# Dazzle_v1.net
KiCad netlist of a schematic drawn in EAGLE
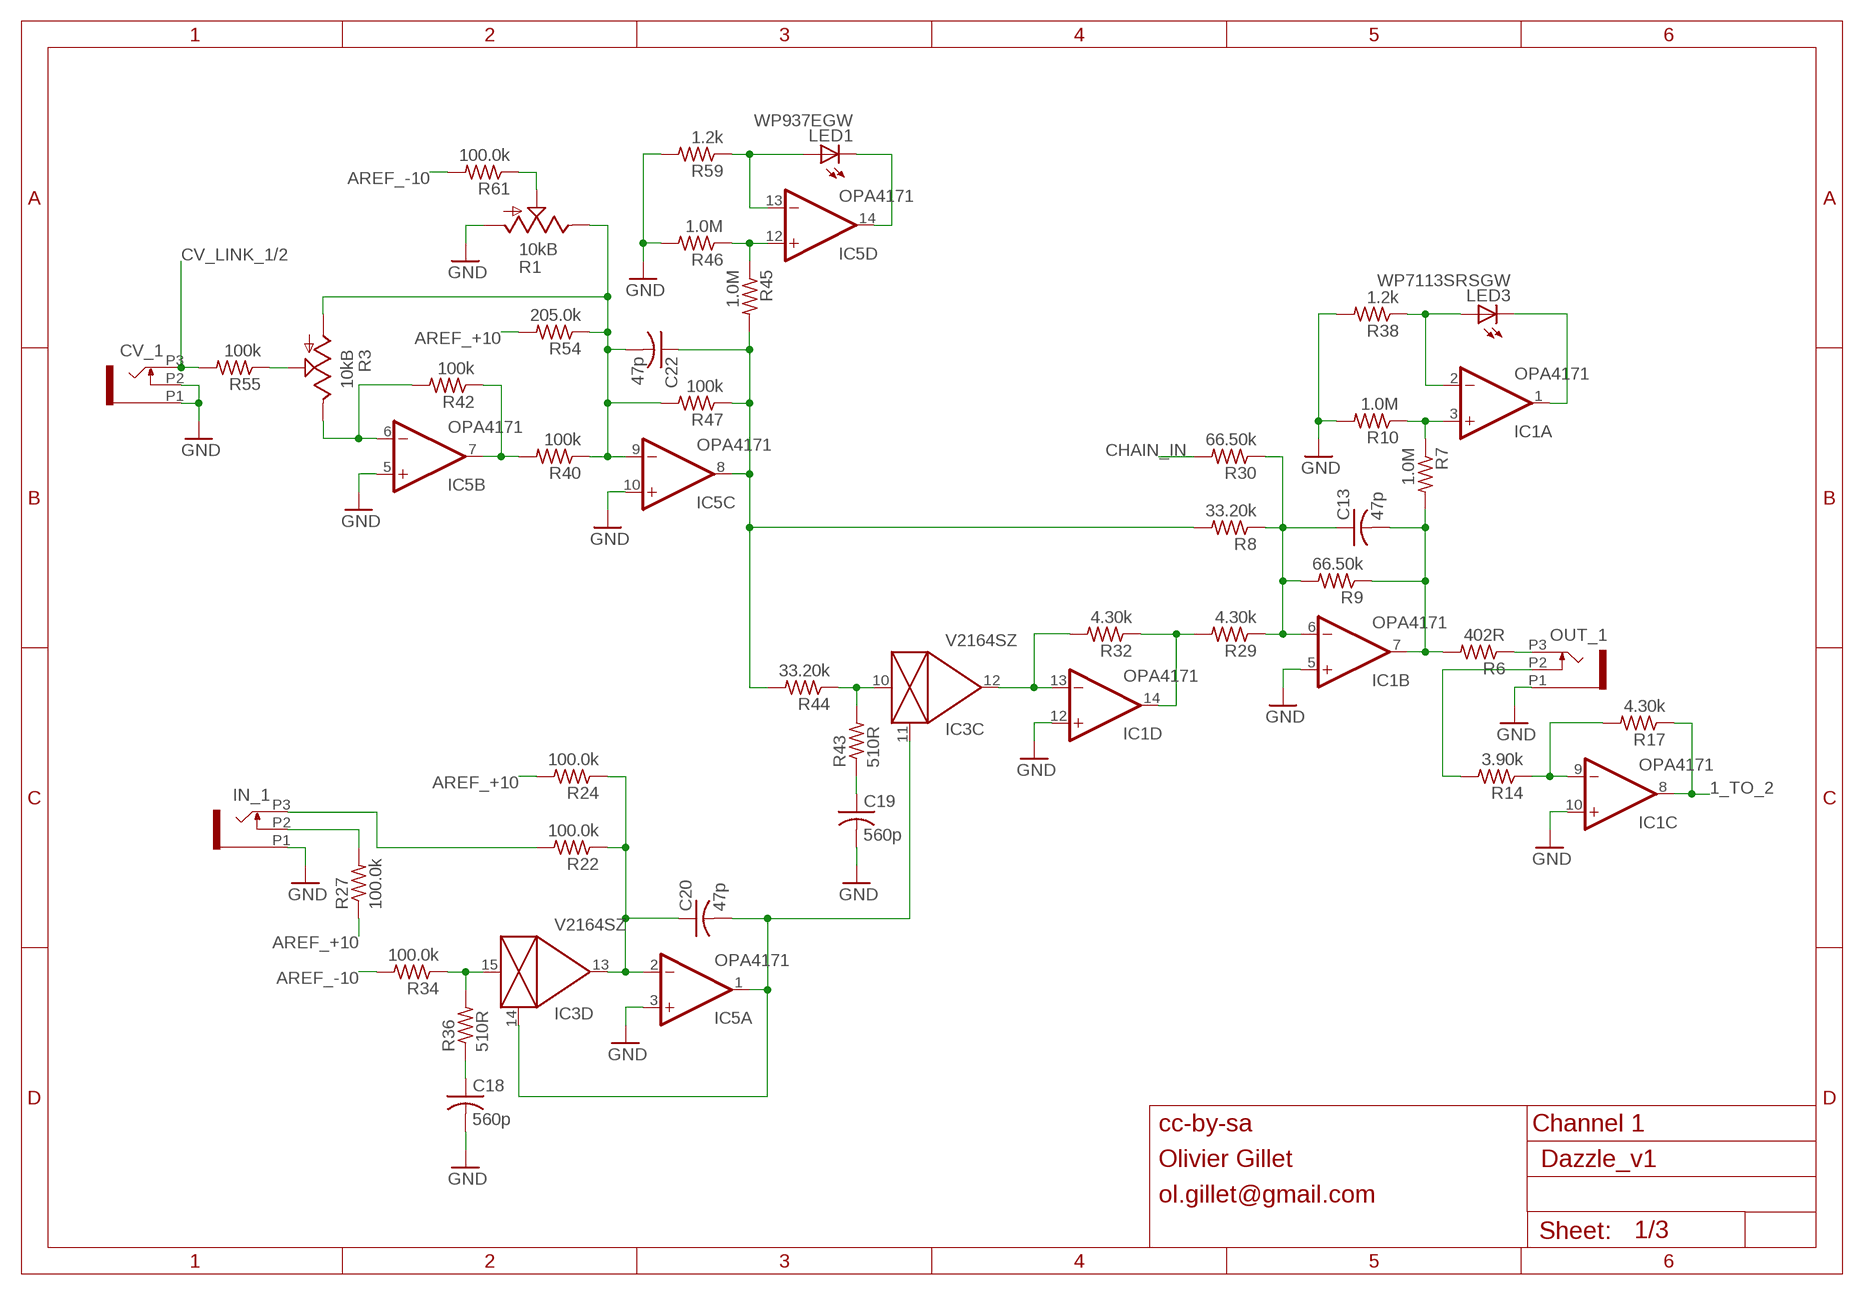
[diagram p0: schematic, sheet 1]
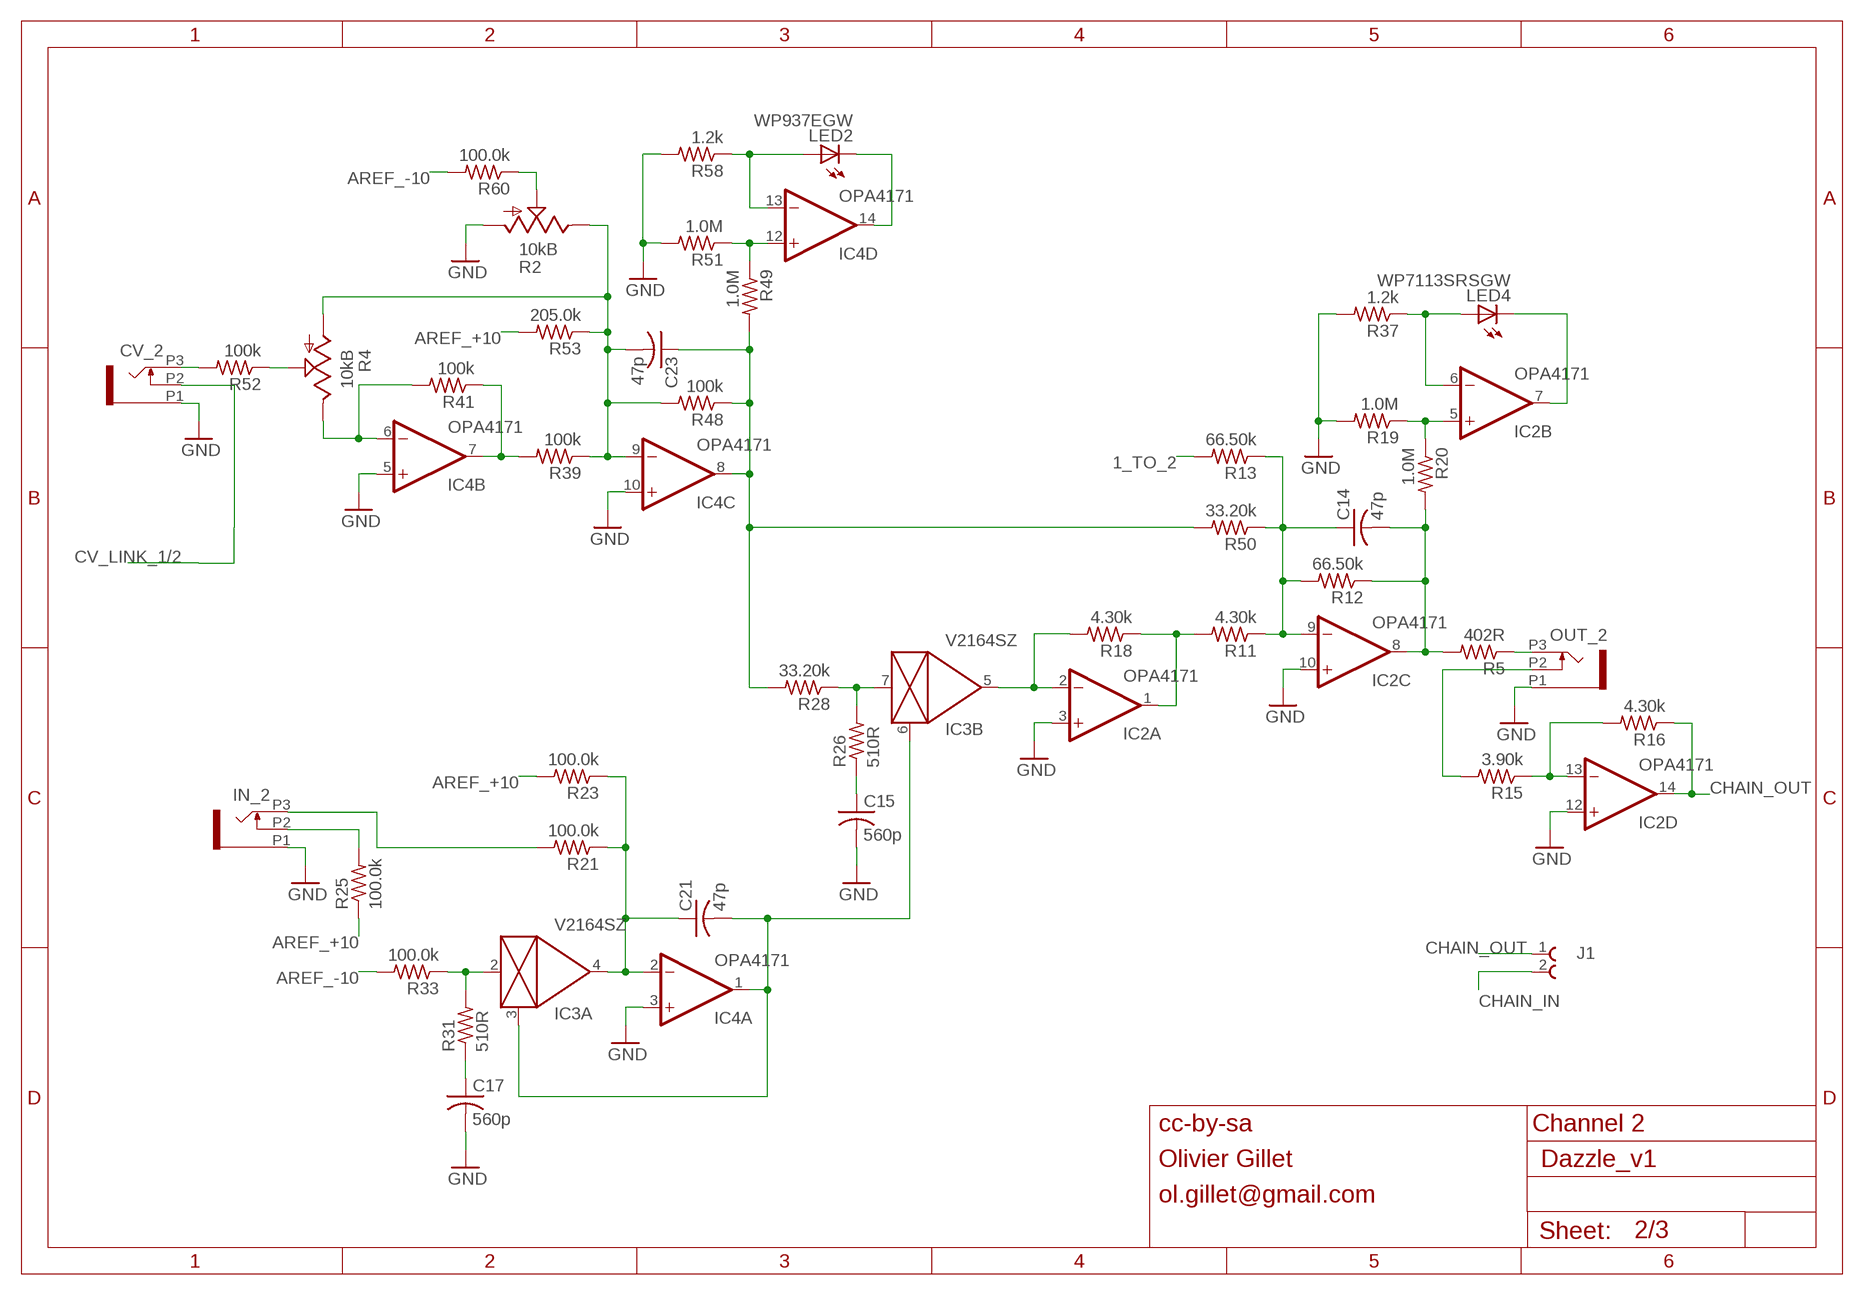
[diagram p1: schematic, sheet 2]
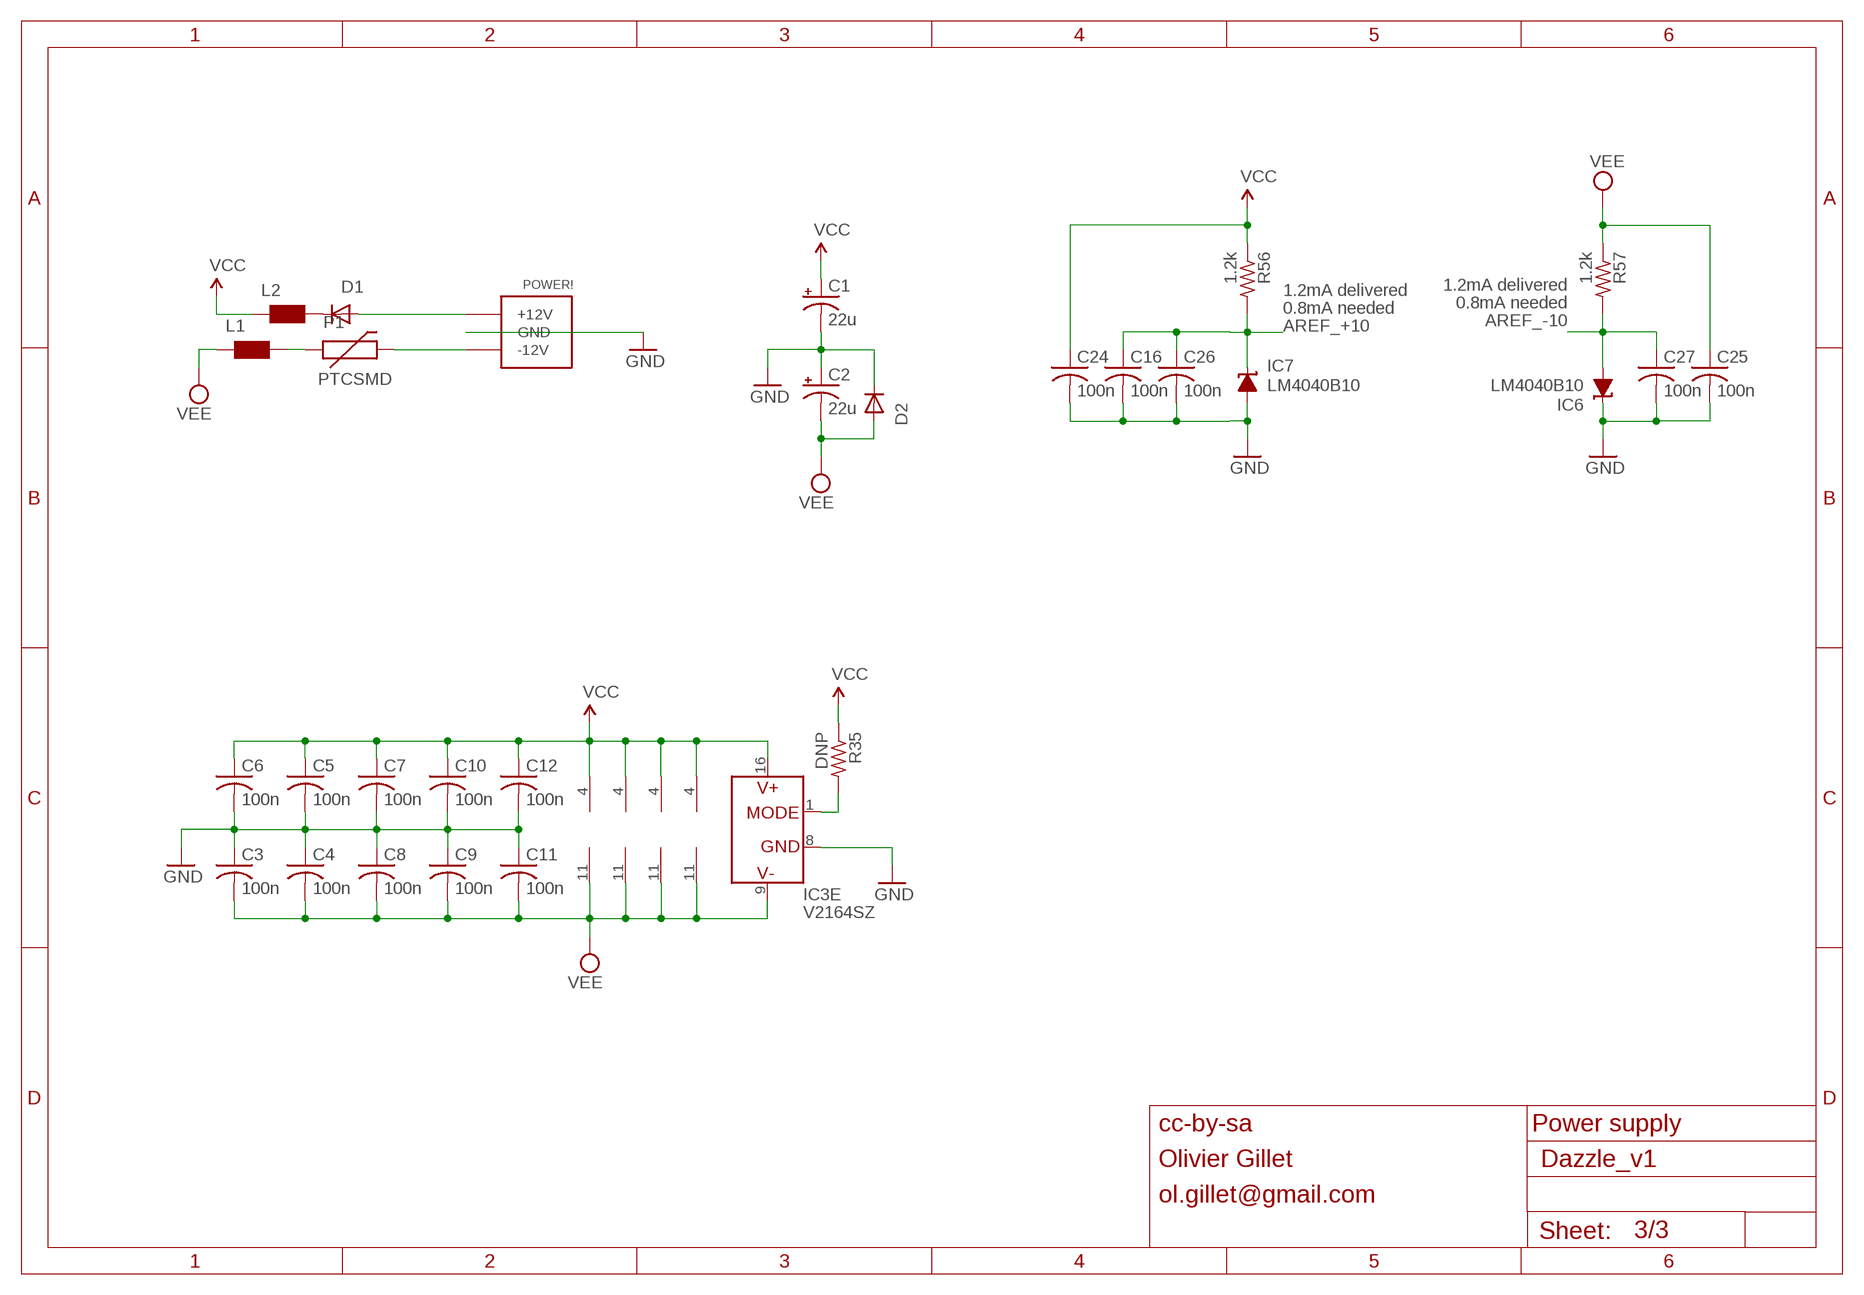
[diagram p2: schematic, sheet 3]

(export (version "E")
  (design (tool "Eeschema 10.0.6"))
  (components
    (comp (ref "C13")
      (value "47p")
      (footprint "eagle-import:C0603")
      (libsource (lib "eagle-import") (part "C-USC0603"))
    )
    (comp (ref "C18")
      (value "560p")
      (footprint "eagle-import:C0603")
      (libsource (lib "eagle-import") (part "C-USC0603"))
    )
    (comp (ref "C19")
      (value "560p")
      (footprint "eagle-import:C0603")
      (libsource (lib "eagle-import") (part "C-USC0603"))
    )
    (comp (ref "C20")
      (value "47p")
      (footprint "eagle-import:C0603")
      (libsource (lib "eagle-import") (part "C-USC0603"))
    )
    (comp (ref "C22")
      (value "47p")
      (footprint "eagle-import:C0603")
      (libsource (lib "eagle-import") (part "C-USC0603"))
    )
    (comp (ref "CV_1")
      (value "OG-PJ301_PJ301_THONKICONN")
      (footprint "eagle-import:OG-PJ301_WQP_PJ_301M6_NO_HOLE")
      (libsource (lib "eagle-import") (part "OG-PJ301_PJ301_THONKICONN"))
    )
    (comp (ref "IC1")
      (value "OPA4171")
      (footprint "eagle-import:TSSOP14")
      (libsource (lib "eagle-import") (part "TL074PW"))
    )
    (comp (ref "IC3")
      (value "V2164SZ")
      (footprint "eagle-import:SOIC16N")
      (libsource (lib "eagle-import") (part "SSM2164S"))
    )
    (comp (ref "IC5")
      (value "OPA4171")
      (footprint "eagle-import:TSSOP14")
      (libsource (lib "eagle-import") (part "TL074PW"))
    )
    (comp (ref "IN_1")
      (value "OG-PJ301_PJ301_THONKICONN")
      (footprint "eagle-import:OG-PJ301_WQP_PJ_301M6_NO_HOLE")
      (libsource (lib "eagle-import") (part "OG-PJ301_PJ301_THONKICONN"))
    )
    (comp (ref "LED1")
      (value "WP937EGW")
      (footprint "eagle-import:LED3MM")
      (libsource (lib "eagle-import") (part "LED3MM"))
    )
    (comp (ref "LED3")
      (value "WP7113SRSGW")
      (footprint "eagle-import:LED5MM")
      (libsource (lib "eagle-import") (part "LED5MM"))
    )
    (comp (ref "OUT_1")
      (value "OG-PJ301_PJ301_THONKICONN")
      (footprint "eagle-import:OG-PJ301_WQP_PJ_301M6_NO_HOLE")
      (libsource (lib "eagle-import") (part "OG-PJ301_PJ301_THONKICONN"))
    )
    (comp (ref "R1")
      (value "10kB")
      (footprint "eagle-import:ALPS_POT_VERTICAL_PS")
      (libsource (lib "eagle-import") (part "POT_USVERTICAL_PS"))
    )
    (comp (ref "R3")
      (value "10kB")
      (footprint "eagle-import:POT-ALPS_ALPS_POT_VERTICAL_PS")
      (libsource (lib "eagle-import") (part "POT-ALPS_POT_USVERTICAL_PS"))
    )
    (comp (ref "R6")
      (value "402R")
      (footprint "eagle-import:R0603")
      (libsource (lib "eagle-import") (part "R-US_R0603"))
    )
    (comp (ref "R7")
      (value "1.0M")
      (footprint "eagle-import:R0603")
      (libsource (lib "eagle-import") (part "R-US_R0603"))
    )
    (comp (ref "R8")
      (value "33.20k")
      (footprint "eagle-import:R0603")
      (libsource (lib "eagle-import") (part "R-US_R0603"))
    )
    (comp (ref "R9")
      (value "66.50k")
      (footprint "eagle-import:R0603")
      (libsource (lib "eagle-import") (part "R-US_R0603"))
    )
    (comp (ref "R10")
      (value "1.0M")
      (footprint "eagle-import:R0603")
      (libsource (lib "eagle-import") (part "R-US_R0603"))
    )
    (comp (ref "R14")
      (value "3.90k")
      (footprint "eagle-import:R0603")
      (libsource (lib "eagle-import") (part "R-US_R0603"))
    )
    (comp (ref "R17")
      (value "4.30k")
      (footprint "eagle-import:R0603")
      (libsource (lib "eagle-import") (part "R-US_R0603"))
    )
    (comp (ref "R22")
      (value "100.0k")
      (footprint "eagle-import:R0603")
      (libsource (lib "eagle-import") (part "R-US_R0603"))
    )
    (comp (ref "R24")
      (value "100.0k")
      (footprint "eagle-import:R0603")
      (libsource (lib "eagle-import") (part "R-US_R0603"))
    )
    (comp (ref "R27")
      (value "100.0k")
      (footprint "eagle-import:R0603")
      (libsource (lib "eagle-import") (part "R-US_R0603"))
    )
    (comp (ref "R29")
      (value "4.30k")
      (footprint "eagle-import:R0603")
      (libsource (lib "eagle-import") (part "R-US_R0603"))
    )
    (comp (ref "R30")
      (value "66.50k")
      (footprint "eagle-import:R0603")
      (libsource (lib "eagle-import") (part "R-US_R0603"))
    )
    (comp (ref "R32")
      (value "4.30k")
      (footprint "eagle-import:R0603")
      (libsource (lib "eagle-import") (part "R-US_R0603"))
    )
    (comp (ref "R34")
      (value "100.0k")
      (footprint "eagle-import:R0603")
      (libsource (lib "eagle-import") (part "R-US_R0603"))
    )
    (comp (ref "R36")
      (value "510R")
      (footprint "eagle-import:R0603")
      (libsource (lib "eagle-import") (part "R-US_R0603"))
    )
    (comp (ref "R38")
      (value "1.2k")
      (footprint "eagle-import:R0603")
      (libsource (lib "eagle-import") (part "R-US_R0603"))
    )
    (comp (ref "R40")
      (value "100k")
      (footprint "eagle-import:R0603")
      (libsource (lib "eagle-import") (part "R-US_R0603"))
    )
    (comp (ref "R42")
      (value "100k")
      (footprint "eagle-import:R0603")
      (libsource (lib "eagle-import") (part "R-US_R0603"))
    )
    (comp (ref "R43")
      (value "510R")
      (footprint "eagle-import:R0603")
      (libsource (lib "eagle-import") (part "R-US_R0603"))
    )
    (comp (ref "R44")
      (value "33.20k")
      (footprint "eagle-import:R0603")
      (libsource (lib "eagle-import") (part "R-US_R0603"))
    )
    (comp (ref "R45")
      (value "1.0M")
      (footprint "eagle-import:R0603")
      (libsource (lib "eagle-import") (part "R-US_R0603"))
    )
    (comp (ref "R46")
      (value "1.0M")
      (footprint "eagle-import:R0603")
      (libsource (lib "eagle-import") (part "R-US_R0603"))
    )
    (comp (ref "R47")
      (value "100k")
      (footprint "eagle-import:R0603")
      (libsource (lib "eagle-import") (part "R-US_R0603"))
    )
    (comp (ref "R54")
      (value "205.0k")
      (footprint "eagle-import:R0603")
      (libsource (lib "eagle-import") (part "R-US_R0603"))
    )
    (comp (ref "R55")
      (value "100k")
      (footprint "eagle-import:R0603")
      (libsource (lib "eagle-import") (part "R-US_R0603"))
    )
    (comp (ref "R59")
      (value "1.2k")
      (footprint "eagle-import:R0603")
      (libsource (lib "eagle-import") (part "R-US_R0603"))
    )
    (comp (ref "R61")
      (value "100.0k")
      (footprint "eagle-import:R0603")
      (libsource (lib "eagle-import") (part "R-US_R0603"))
    )
    (comp (ref "C1")
      (value "22u")
      (footprint "eagle-import:PANASONIC_C")
      (libsource (lib "eagle-import") (part "CPOL-USC"))
    )
    (comp (ref "C2")
      (value "22u")
      (footprint "eagle-import:PANASONIC_C")
      (libsource (lib "eagle-import") (part "CPOL-USC"))
    )
    (comp (ref "C3")
      (value "100n")
      (footprint "eagle-import:C0603")
      (libsource (lib "eagle-import") (part "C-USC0603"))
    )
    (comp (ref "C4")
      (value "100n")
      (footprint "eagle-import:C0603")
      (libsource (lib "eagle-import") (part "C-USC0603"))
    )
    (comp (ref "C5")
      (value "100n")
      (footprint "eagle-import:C0603")
      (libsource (lib "eagle-import") (part "C-USC0603"))
    )
    (comp (ref "C6")
      (value "100n")
      (footprint "eagle-import:C0603")
      (libsource (lib "eagle-import") (part "C-USC0603"))
    )
    (comp (ref "C7")
      (value "100n")
      (footprint "eagle-import:C0603")
      (libsource (lib "eagle-import") (part "C-USC0603"))
    )
    (comp (ref "C8")
      (value "100n")
      (footprint "eagle-import:C0603")
      (libsource (lib "eagle-import") (part "C-USC0603"))
    )
    (comp (ref "C9")
      (value "100n")
      (footprint "eagle-import:C0603")
      (libsource (lib "eagle-import") (part "C-USC0603"))
    )
    (comp (ref "C10")
      (value "100n")
      (footprint "eagle-import:C0603")
      (libsource (lib "eagle-import") (part "C-USC0603"))
    )
    (comp (ref "C11")
      (value "100n")
      (footprint "eagle-import:C0603")
      (libsource (lib "eagle-import") (part "C-USC0603"))
    )
    (comp (ref "C12")
      (value "100n")
      (footprint "eagle-import:C0603")
      (libsource (lib "eagle-import") (part "C-USC0603"))
    )
    (comp (ref "C16")
      (value "100n")
      (footprint "eagle-import:C0603")
      (libsource (lib "eagle-import") (part "C-USC0603"))
    )
    (comp (ref "C24")
      (value "100n")
      (footprint "eagle-import:C0603")
      (libsource (lib "eagle-import") (part "C-USC0603"))
    )
    (comp (ref "C25")
      (value "100n")
      (footprint "eagle-import:C0603")
      (libsource (lib "eagle-import") (part "C-USC0603"))
    )
    (comp (ref "C26")
      (value "100n")
      (footprint "eagle-import:C0603")
      (libsource (lib "eagle-import") (part "C-USC0603"))
    )
    (comp (ref "C27")
      (value "100n")
      (footprint "eagle-import:C0603")
      (libsource (lib "eagle-import") (part "C-USC0603"))
    )
    (comp (ref "D1")
      (value "1N5819HW")
      (footprint "eagle-import:SOD123")
      (libsource (lib "eagle-import") (part "DIODE-SOD123"))
    )
    (comp (ref "D2")
      (value "1N5819HW")
      (footprint "eagle-import:SOD123")
      (libsource (lib "eagle-import") (part "DIODE-SOD123"))
    )
    (comp (ref "IC2")
      (value "OPA4171")
      (footprint "eagle-import:TSSOP14")
      (libsource (lib "eagle-import") (part "TL074PW"))
    )
    (comp (ref "IC4")
      (value "OPA4171")
      (footprint "eagle-import:TSSOP14")
      (libsource (lib "eagle-import") (part "TL074PW"))
    )
    (comp (ref "IC6")
      (value "LM4040B10")
      (footprint "eagle-import:DBZ_R-PDSO-G3")
      (libsource (lib "eagle-import") (part "LM4041DBZB12"))
    )
    (comp (ref "IC7")
      (value "LM4040B10")
      (footprint "eagle-import:DBZ_R-PDSO-G3")
      (libsource (lib "eagle-import") (part "LM4041DBZB12"))
    )
    (comp (ref "L1")
      (value "WE-CBF_0603")
      (footprint "eagle-import:0603")
      (libsource (lib "eagle-import") (part "WE-CBF_0603"))
    )
    (comp (ref "L2")
      (value "WE-CBF_0603")
      (footprint "eagle-import:0603")
      (libsource (lib "eagle-import") (part "WE-CBF_0603"))
    )
    (comp (ref "P1")
      (value "PTCSMD")
      (footprint "eagle-import:PTC-1206")
      (libsource (lib "eagle-import") (part "PTCSMD"))
    )
    (comp (ref "POWER!")
      (value "POWER_SIMPLE")
      (footprint "eagle-import:2X05_SMT_HEADER")
      (libsource (lib "eagle-import") (part "POWER_SIMPLE"))
    )
    (comp (ref "R35")
      (value "DNP")
      (footprint "eagle-import:R0603")
      (libsource (lib "eagle-import") (part "R-US_R0603"))
    )
    (comp (ref "R56")
      (value "1.2k")
      (footprint "eagle-import:R0603")
      (libsource (lib "eagle-import") (part "R-US_R0603"))
    )
    (comp (ref "R57")
      (value "1.2k")
      (footprint "eagle-import:R0603")
      (libsource (lib "eagle-import") (part "R-US_R0603"))
    )
    (comp (ref "C14")
      (value "47p")
      (footprint "eagle-import:C0603")
      (libsource (lib "eagle-import") (part "C-USC0603"))
    )
    (comp (ref "C15")
      (value "560p")
      (footprint "eagle-import:C0603")
      (libsource (lib "eagle-import") (part "C-USC0603"))
    )
    (comp (ref "C17")
      (value "560p")
      (footprint "eagle-import:C0603")
      (libsource (lib "eagle-import") (part "C-USC0603"))
    )
    (comp (ref "C21")
      (value "47p")
      (footprint "eagle-import:C0603")
      (libsource (lib "eagle-import") (part "C-USC0603"))
    )
    (comp (ref "C23")
      (value "47p")
      (footprint "eagle-import:C0603")
      (libsource (lib "eagle-import") (part "C-USC0603"))
    )
    (comp (ref "CV_2")
      (value "OG-PJ301_PJ301_THONKICONN")
      (footprint "eagle-import:OG-PJ301_WQP_PJ_301M6_NO_HOLE")
      (libsource (lib "eagle-import") (part "OG-PJ301_PJ301_THONKICONN"))
    )
    (comp (ref "IN_2")
      (value "OG-PJ301_PJ301_THONKICONN")
      (footprint "eagle-import:OG-PJ301_WQP_PJ_301M6_NO_HOLE")
      (libsource (lib "eagle-import") (part "OG-PJ301_PJ301_THONKICONN"))
    )
    (comp (ref "J1")
      (value "61300211121")
      (footprint "eagle-import:61300211121")
      (libsource (lib "eagle-import") (part "61300211121"))
    )
    (comp (ref "LED2")
      (value "WP937EGW")
      (footprint "eagle-import:LED3MM")
      (libsource (lib "eagle-import") (part "LED3MM"))
    )
    (comp (ref "LED4")
      (value "WP7113SRSGW")
      (footprint "eagle-import:LED5MM")
      (libsource (lib "eagle-import") (part "LED5MM"))
    )
    (comp (ref "OUT_2")
      (value "OG-PJ301_PJ301_THONKICONN")
      (footprint "eagle-import:OG-PJ301_WQP_PJ_301M6_NO_HOLE")
      (libsource (lib "eagle-import") (part "OG-PJ301_PJ301_THONKICONN"))
    )
    (comp (ref "R2")
      (value "10kB")
      (footprint "eagle-import:ALPS_POT_VERTICAL_PS")
      (libsource (lib "eagle-import") (part "POT_USVERTICAL_PS"))
    )
    (comp (ref "R4")
      (value "10kB")
      (footprint "eagle-import:POT-ALPS_ALPS_POT_VERTICAL_PS")
      (libsource (lib "eagle-import") (part "POT-ALPS_POT_USVERTICAL_PS"))
    )
    (comp (ref "R5")
      (value "402R")
      (footprint "eagle-import:R0603")
      (libsource (lib "eagle-import") (part "R-US_R0603"))
    )
    (comp (ref "R11")
      (value "4.30k")
      (footprint "eagle-import:R0603")
      (libsource (lib "eagle-import") (part "R-US_R0603"))
    )
    (comp (ref "R12")
      (value "66.50k")
      (footprint "eagle-import:R0603")
      (libsource (lib "eagle-import") (part "R-US_R0603"))
    )
    (comp (ref "R13")
      (value "66.50k")
      (footprint "eagle-import:R0603")
      (libsource (lib "eagle-import") (part "R-US_R0603"))
    )
    (comp (ref "R15")
      (value "3.90k")
      (footprint "eagle-import:R0603")
      (libsource (lib "eagle-import") (part "R-US_R0603"))
    )
    (comp (ref "R16")
      (value "4.30k")
      (footprint "eagle-import:R0603")
      (libsource (lib "eagle-import") (part "R-US_R0603"))
    )
    (comp (ref "R18")
      (value "4.30k")
      (footprint "eagle-import:R0603")
      (libsource (lib "eagle-import") (part "R-US_R0603"))
    )
    (comp (ref "R19")
      (value "1.0M")
      (footprint "eagle-import:R0603")
      (libsource (lib "eagle-import") (part "R-US_R0603"))
    )
    (comp (ref "R20")
      (value "1.0M")
      (footprint "eagle-import:R0603")
      (libsource (lib "eagle-import") (part "R-US_R0603"))
    )
    (comp (ref "R21")
      (value "100.0k")
      (footprint "eagle-import:R0603")
      (libsource (lib "eagle-import") (part "R-US_R0603"))
    )
    (comp (ref "R23")
      (value "100.0k")
      (footprint "eagle-import:R0603")
      (libsource (lib "eagle-import") (part "R-US_R0603"))
    )
    (comp (ref "R25")
      (value "100.0k")
      (footprint "eagle-import:R0603")
      (libsource (lib "eagle-import") (part "R-US_R0603"))
    )
    (comp (ref "R26")
      (value "510R")
      (footprint "eagle-import:R0603")
      (libsource (lib "eagle-import") (part "R-US_R0603"))
    )
    (comp (ref "R28")
      (value "33.20k")
      (footprint "eagle-import:R0603")
      (libsource (lib "eagle-import") (part "R-US_R0603"))
    )
    (comp (ref "R31")
      (value "510R")
      (footprint "eagle-import:R0603")
      (libsource (lib "eagle-import") (part "R-US_R0603"))
    )
    (comp (ref "R33")
      (value "100.0k")
      (footprint "eagle-import:R0603")
      (libsource (lib "eagle-import") (part "R-US_R0603"))
    )
    (comp (ref "R37")
      (value "1.2k")
      (footprint "eagle-import:R0603")
      (libsource (lib "eagle-import") (part "R-US_R0603"))
    )
    (comp (ref "R39")
      (value "100k")
      (footprint "eagle-import:R0603")
      (libsource (lib "eagle-import") (part "R-US_R0603"))
    )
    (comp (ref "R41")
      (value "100k")
      (footprint "eagle-import:R0603")
      (libsource (lib "eagle-import") (part "R-US_R0603"))
    )
    (comp (ref "R48")
      (value "100k")
      (footprint "eagle-import:R0603")
      (libsource (lib "eagle-import") (part "R-US_R0603"))
    )
    (comp (ref "R49")
      (value "1.0M")
      (footprint "eagle-import:R0603")
      (libsource (lib "eagle-import") (part "R-US_R0603"))
    )
    (comp (ref "R50")
      (value "33.20k")
      (footprint "eagle-import:R0603")
      (libsource (lib "eagle-import") (part "R-US_R0603"))
    )
    (comp (ref "R51")
      (value "1.0M")
      (footprint "eagle-import:R0603")
      (libsource (lib "eagle-import") (part "R-US_R0603"))
    )
    (comp (ref "R52")
      (value "100k")
      (footprint "eagle-import:R0603")
      (libsource (lib "eagle-import") (part "R-US_R0603"))
    )
    (comp (ref "R53")
      (value "205.0k")
      (footprint "eagle-import:R0603")
      (libsource (lib "eagle-import") (part "R-US_R0603"))
    )
    (comp (ref "R58")
      (value "1.2k")
      (footprint "eagle-import:R0603")
      (libsource (lib "eagle-import") (part "R-US_R0603"))
    )
    (comp (ref "R60")
      (value "100.0k")
      (footprint "eagle-import:R0603")
      (libsource (lib "eagle-import") (part "R-US_R0603"))
    )
  )
  (nets
    (net (code "1") (name "1_TO_2") (class "Default")
      (node (ref "IC1") (pin "8") (pinfunction "OUT_8") (pintype "output"))
      (node (ref "R13") (pin "2") (pinfunction "2_2") (pintype "passive"))
      (node (ref "R17") (pin "1") (pinfunction "1_1") (pintype "passive"))
    )
    (net (code "2") (name "AREF_+10") (class "Default")
      (node (ref "C16") (pin "1") (pinfunction "1_1") (pintype "passive"))
      (node (ref "C26") (pin "1") (pinfunction "1_1") (pintype "passive"))
      (node (ref "IC7") (pin "1") (pinfunction "C_1") (pintype "passive"))
      (node (ref "R23") (pin "2") (pinfunction "2_2") (pintype "passive"))
      (node (ref "R24") (pin "2") (pinfunction "2_2") (pintype "passive"))
      (node (ref "R25") (pin "1") (pinfunction "1_1") (pintype "passive"))
      (node (ref "R27") (pin "1") (pinfunction "1_1") (pintype "passive"))
      (node (ref "R53") (pin "2") (pinfunction "2_2") (pintype "passive"))
      (node (ref "R54") (pin "2") (pinfunction "2_2") (pintype "passive"))
      (node (ref "R56") (pin "2") (pinfunction "2_2") (pintype "passive"))
    )
    (net (code "3") (name "AREF_-10") (class "Default")
      (node (ref "C27") (pin "1") (pinfunction "1_1") (pintype "passive"))
      (node (ref "IC6") (pin "2") (pinfunction "A_2") (pintype "passive"))
      (node (ref "R33") (pin "2") (pinfunction "2_2") (pintype "passive"))
      (node (ref "R34") (pin "2") (pinfunction "2_2") (pintype "passive"))
      (node (ref "R57") (pin "2") (pinfunction "2_2") (pintype "passive"))
      (node (ref "R60") (pin "2") (pinfunction "2_2") (pintype "passive"))
      (node (ref "R61") (pin "2") (pinfunction "2_2") (pintype "passive"))
    )
    (net (code "4") (name "CHAIN_IN") (class "Default")
      (node (ref "J1") (pin "2") (pinfunction "2_2") (pintype "passive"))
      (node (ref "R30") (pin "2") (pinfunction "2_2") (pintype "passive"))
    )
    (net (code "5") (name "CHAIN_OUT") (class "Default")
      (node (ref "IC2") (pin "14") (pinfunction "OUT_14") (pintype "output"))
      (node (ref "J1") (pin "1") (pinfunction "1_1") (pintype "passive"))
      (node (ref "R16") (pin "1") (pinfunction "1_1") (pintype "passive"))
    )
    (net (code "6") (name "CV_LINK_1{slash}2") (class "Default")
      (node (ref "CV_1") (pin "P3") (pinfunction "3_P3") (pintype "passive"))
      (node (ref "CV_2") (pin "P2") (pinfunction "2_P2") (pintype "passive"))
      (node (ref "R55") (pin "2") (pinfunction "2_2") (pintype "passive"))
    )
    (net (code "7") (name "GND") (class "Default")
      (node (ref "C1") (pin "-") (pinfunction "-_-") (pintype "passive"))
      (node (ref "C10") (pin "2") (pinfunction "2_2") (pintype "passive"))
      (node (ref "C11") (pin "1") (pinfunction "1_1") (pintype "passive"))
      (node (ref "C12") (pin "2") (pinfunction "2_2") (pintype "passive"))
      (node (ref "C15") (pin "2") (pinfunction "2_2") (pintype "passive"))
      (node (ref "C16") (pin "2") (pinfunction "2_2") (pintype "passive"))
      (node (ref "C17") (pin "2") (pinfunction "2_2") (pintype "passive"))
      (node (ref "C18") (pin "2") (pinfunction "2_2") (pintype "passive"))
      (node (ref "C19") (pin "2") (pinfunction "2_2") (pintype "passive"))
      (node (ref "C2") (pin "+") (pinfunction "+_+") (pintype "passive"))
      (node (ref "C24") (pin "2") (pinfunction "2_2") (pintype "passive"))
      (node (ref "C25") (pin "2") (pinfunction "2_2") (pintype "passive"))
      (node (ref "C26") (pin "2") (pinfunction "2_2") (pintype "passive"))
      (node (ref "C27") (pin "2") (pinfunction "2_2") (pintype "passive"))
      (node (ref "C3") (pin "1") (pinfunction "1_1") (pintype "passive"))
      (node (ref "C4") (pin "1") (pinfunction "1_1") (pintype "passive"))
      (node (ref "C5") (pin "2") (pinfunction "2_2") (pintype "passive"))
      (node (ref "C6") (pin "2") (pinfunction "2_2") (pintype "passive"))
      (node (ref "C7") (pin "2") (pinfunction "2_2") (pintype "passive"))
      (node (ref "C8") (pin "1") (pinfunction "1_1") (pintype "passive"))
      (node (ref "C9") (pin "1") (pinfunction "1_1") (pintype "passive"))
      (node (ref "CV_1") (pin "P1") (pinfunction "1_P1") (pintype "passive"))
      (node (ref "CV_1") (pin "P2") (pinfunction "2_P2") (pintype "passive"))
      (node (ref "CV_2") (pin "P1") (pinfunction "1_P1") (pintype "passive"))
      (node (ref "D2") (pin "C") (pinfunction "C_C") (pintype "passive"))
      (node (ref "IC1") (pin "10") (pinfunction "+IN_10") (pintype "input"))
      (node (ref "IC1") (pin "12") (pinfunction "+IN_12") (pintype "input"))
      (node (ref "IC1") (pin "5") (pinfunction "+IN_5") (pintype "input"))
      (node (ref "IC2") (pin "10") (pinfunction "+IN_10") (pintype "input"))
      (node (ref "IC2") (pin "12") (pinfunction "+IN_12") (pintype "input"))
      (node (ref "IC2") (pin "3") (pinfunction "+IN_3") (pintype "input"))
      (node (ref "IC3") (pin "8") (pinfunction "GND_8") (pintype "power_in"))
      (node (ref "IC4") (pin "10") (pinfunction "+IN_10") (pintype "input"))
      (node (ref "IC4") (pin "3") (pinfunction "+IN_3") (pintype "input"))
      (node (ref "IC4") (pin "5") (pinfunction "+IN_5") (pintype "input"))
      (node (ref "IC5") (pin "10") (pinfunction "+IN_10") (pintype "input"))
      (node (ref "IC5") (pin "3") (pinfunction "+IN_3") (pintype "input"))
      (node (ref "IC5") (pin "5") (pinfunction "+IN_5") (pintype "input"))
      (node (ref "IC6") (pin "1") (pinfunction "C_1") (pintype "passive"))
      (node (ref "IC7") (pin "2") (pinfunction "A_2") (pintype "passive"))
      (node (ref "IN_1") (pin "P1") (pinfunction "1_P1") (pintype "passive"))
      (node (ref "IN_2") (pin "P1") (pinfunction "1_P1") (pintype "passive"))
      (node (ref "OUT_1") (pin "P1") (pinfunction "1_P1") (pintype "passive"))
      (node (ref "OUT_2") (pin "P1") (pinfunction "1_P1") (pintype "passive"))
      (node (ref "POWER!") (pin "3") (pinfunction "GND_3") (pintype "bidirectional"))
      (node (ref "POWER!") (pin "4") (pinfunction "GND_4") (pintype "bidirectional"))
      (node (ref "POWER!") (pin "5") (pinfunction "GND_5") (pintype "bidirectional"))
      (node (ref "POWER!") (pin "6") (pinfunction "GND_6") (pintype "bidirectional"))
      (node (ref "POWER!") (pin "7") (pinfunction "GND_7") (pintype "bidirectional"))
      (node (ref "POWER!") (pin "8") (pinfunction "GND_8") (pintype "bidirectional"))
      (node (ref "R1") (pin "P$3") (pinfunction "A_P$3") (pintype "passive"))
      (node (ref "R10") (pin "2") (pinfunction "2_2") (pintype "passive"))
      (node (ref "R19") (pin "2") (pinfunction "2_2") (pintype "passive"))
      (node (ref "R2") (pin "P$3") (pinfunction "A_P$3") (pintype "passive"))
      (node (ref "R37") (pin "2") (pinfunction "2_2") (pintype "passive"))
      (node (ref "R38") (pin "2") (pinfunction "2_2") (pintype "passive"))
      (node (ref "R46") (pin "2") (pinfunction "2_2") (pintype "passive"))
      (node (ref "R51") (pin "2") (pinfunction "2_2") (pintype "passive"))
      (node (ref "R58") (pin "2") (pinfunction "2_2") (pintype "passive"))
      (node (ref "R59") (pin "2") (pinfunction "2_2") (pintype "passive"))
    )
    (net (code "8") (name "Net-(C15-Pad1)") (class "Default")
      (node (ref "C15") (pin "1") (pinfunction "1_1") (pintype "passive"))
      (node (ref "R26") (pin "1") (pinfunction "1_1") (pintype "passive"))
    )
    (net (code "9") (name "Net-(C17-Pad1)") (class "Default")
      (node (ref "C17") (pin "1") (pinfunction "1_1") (pintype "passive"))
      (node (ref "R31") (pin "1") (pinfunction "1_1") (pintype "passive"))
    )
    (net (code "10") (name "Net-(C18-Pad1)") (class "Default")
      (node (ref "C18") (pin "1") (pinfunction "1_1") (pintype "passive"))
      (node (ref "R36") (pin "1") (pinfunction "1_1") (pintype "passive"))
    )
    (net (code "11") (name "Net-(C19-Pad1)") (class "Default")
      (node (ref "C19") (pin "1") (pinfunction "1_1") (pintype "passive"))
      (node (ref "R43") (pin "1") (pinfunction "1_1") (pintype "passive"))
    )
    (net (code "12") (name "Net-(CV_2-3)") (class "Default")
      (node (ref "CV_2") (pin "P3") (pinfunction "3_P3") (pintype "passive"))
      (node (ref "R52") (pin "2") (pinfunction "2_2") (pintype "passive"))
    )
    (net (code "13") (name "Net-(D1-PadA)") (class "Default")
      (node (ref "D1") (pin "A") (pinfunction "A_A") (pintype "passive"))
      (node (ref "POWER!") (pin "10") (pinfunction "+12V_10") (pintype "bidirectional"))
      (node (ref "POWER!") (pin "9") (pinfunction "+12V_9") (pintype "bidirectional"))
    )
    (net (code "14") (name "Net-(D1-PadC)") (class "Default")
      (node (ref "D1") (pin "C") (pinfunction "C_C") (pintype "passive"))
      (node (ref "L2") (pin "2") (pinfunction "2_2") (pintype "passive"))
    )
    (net (code "15") (name "Net-(IC1A-+IN)") (class "Default")
      (node (ref "IC1") (pin "3") (pinfunction "+IN_3") (pintype "input"))
      (node (ref "R10") (pin "1") (pinfunction "1_1") (pintype "passive"))
      (node (ref "R7") (pin "1") (pinfunction "1_1") (pintype "passive"))
    )
    (net (code "16") (name "Net-(IC1A--IN)") (class "Default")
      (node (ref "IC1") (pin "2") (pinfunction "-IN_2") (pintype "input"))
      (node (ref "LED3") (pin "A") (pinfunction "A_A") (pintype "passive"))
      (node (ref "R38") (pin "1") (pinfunction "1_1") (pintype "passive"))
    )
    (net (code "17") (name "Net-(IC1A-OUT)") (class "Default")
      (node (ref "IC1") (pin "1") (pinfunction "OUT_1") (pintype "output"))
      (node (ref "LED3") (pin "K") (pinfunction "C_K") (pintype "passive"))
    )
    (net (code "18") (name "Net-(IC1B--IN)") (class "Default")
      (node (ref "C13") (pin "1") (pinfunction "1_1") (pintype "passive"))
      (node (ref "IC1") (pin "6") (pinfunction "-IN_6") (pintype "input"))
      (node (ref "R29") (pin "1") (pinfunction "1_1") (pintype "passive"))
      (node (ref "R30") (pin "1") (pinfunction "1_1") (pintype "passive"))
      (node (ref "R8") (pin "1") (pinfunction "1_1") (pintype "passive"))
      (node (ref "R9") (pin "2") (pinfunction "2_2") (pintype "passive"))
    )
    (net (code "19") (name "Net-(IC1B-OUT)") (class "Default")
      (node (ref "C13") (pin "2") (pinfunction "2_2") (pintype "passive"))
      (node (ref "IC1") (pin "7") (pinfunction "OUT_7") (pintype "output"))
      (node (ref "R6") (pin "2") (pinfunction "2_2") (pintype "passive"))
      (node (ref "R7") (pin "2") (pinfunction "2_2") (pintype "passive"))
      (node (ref "R9") (pin "1") (pinfunction "1_1") (pintype "passive"))
    )
    (net (code "20") (name "Net-(IC1C--IN)") (class "Default")
      (node (ref "IC1") (pin "9") (pinfunction "-IN_9") (pintype "input"))
      (node (ref "R14") (pin "1") (pinfunction "1_1") (pintype "passive"))
      (node (ref "R17") (pin "2") (pinfunction "2_2") (pintype "passive"))
    )
    (net (code "21") (name "Net-(IC1D--IN)") (class "Default")
      (node (ref "IC1") (pin "13") (pinfunction "-IN_13") (pintype "input"))
      (node (ref "IC3") (pin "12") (pinfunction "OUT_12") (pintype "output"))
      (node (ref "R32") (pin "2") (pinfunction "2_2") (pintype "passive"))
    )
    (net (code "22") (name "Net-(IC1D-OUT)") (class "Default")
      (node (ref "IC1") (pin "14") (pinfunction "OUT_14") (pintype "output"))
      (node (ref "R29") (pin "2") (pinfunction "2_2") (pintype "passive"))
      (node (ref "R32") (pin "1") (pinfunction "1_1") (pintype "passive"))
    )
    (net (code "23") (name "Net-(IC2A--IN)") (class "Default")
      (node (ref "IC2") (pin "2") (pinfunction "-IN_2") (pintype "input"))
      (node (ref "IC3") (pin "5") (pinfunction "OUT_5") (pintype "output"))
      (node (ref "R18") (pin "2") (pinfunction "2_2") (pintype "passive"))
    )
    (net (code "24") (name "Net-(IC2A-OUT)") (class "Default")
      (node (ref "IC2") (pin "1") (pinfunction "OUT_1") (pintype "output"))
      (node (ref "R11") (pin "2") (pinfunction "2_2") (pintype "passive"))
      (node (ref "R18") (pin "1") (pinfunction "1_1") (pintype "passive"))
    )
    (net (code "25") (name "Net-(IC2B-+IN)") (class "Default")
      (node (ref "IC2") (pin "5") (pinfunction "+IN_5") (pintype "input"))
      (node (ref "R19") (pin "1") (pinfunction "1_1") (pintype "passive"))
      (node (ref "R20") (pin "1") (pinfunction "1_1") (pintype "passive"))
    )
    (net (code "26") (name "Net-(IC2B--IN)") (class "Default")
      (node (ref "IC2") (pin "6") (pinfunction "-IN_6") (pintype "input"))
      (node (ref "LED4") (pin "A") (pinfunction "A_A") (pintype "passive"))
      (node (ref "R37") (pin "1") (pinfunction "1_1") (pintype "passive"))
    )
    (net (code "27") (name "Net-(IC2B-OUT)") (class "Default")
      (node (ref "IC2") (pin "7") (pinfunction "OUT_7") (pintype "output"))
      (node (ref "LED4") (pin "K") (pinfunction "C_K") (pintype "passive"))
    )
    (net (code "28") (name "Net-(IC2C--IN)") (class "Default")
      (node (ref "C14") (pin "1") (pinfunction "1_1") (pintype "passive"))
      (node (ref "IC2") (pin "9") (pinfunction "-IN_9") (pintype "input"))
      (node (ref "R11") (pin "1") (pinfunction "1_1") (pintype "passive"))
      (node (ref "R12") (pin "2") (pinfunction "2_2") (pintype "passive"))
      (node (ref "R13") (pin "1") (pinfunction "1_1") (pintype "passive"))
      (node (ref "R50") (pin "1") (pinfunction "1_1") (pintype "passive"))
    )
    (net (code "29") (name "Net-(IC2C-OUT)") (class "Default")
      (node (ref "C14") (pin "2") (pinfunction "2_2") (pintype "passive"))
      (node (ref "IC2") (pin "8") (pinfunction "OUT_8") (pintype "output"))
      (node (ref "R12") (pin "1") (pinfunction "1_1") (pintype "passive"))
      (node (ref "R20") (pin "2") (pinfunction "2_2") (pintype "passive"))
      (node (ref "R5") (pin "2") (pinfunction "2_2") (pintype "passive"))
    )
    (net (code "30") (name "Net-(IC2D--IN)") (class "Default")
      (node (ref "IC2") (pin "13") (pinfunction "-IN_13") (pintype "input"))
      (node (ref "R15") (pin "1") (pinfunction "1_1") (pintype "passive"))
      (node (ref "R16") (pin "2") (pinfunction "2_2") (pintype "passive"))
    )
    (net (code "31") (name "Net-(IC3A-CTRL)") (class "Default")
      (node (ref "C21") (pin "2") (pinfunction "2_2") (pintype "passive"))
      (node (ref "IC3") (pin "3") (pinfunction "CTRL_3") (pintype "input"))
      (node (ref "IC3") (pin "6") (pinfunction "CTRL_6") (pintype "input"))
      (node (ref "IC4") (pin "1") (pinfunction "OUT_1") (pintype "output"))
    )
    (net (code "32") (name "Net-(IC3A-IN)") (class "Default")
      (node (ref "IC3") (pin "2") (pinfunction "IN_2") (pintype "input"))
      (node (ref "R31") (pin "2") (pinfunction "2_2") (pintype "passive"))
      (node (ref "R33") (pin "1") (pinfunction "1_1") (pintype "passive"))
    )
    (net (code "33") (name "Net-(IC3A-OUT)") (class "Default")
      (node (ref "C21") (pin "1") (pinfunction "1_1") (pintype "passive"))
      (node (ref "IC3") (pin "4") (pinfunction "OUT_4") (pintype "output"))
      (node (ref "IC4") (pin "2") (pinfunction "-IN_2") (pintype "input"))
      (node (ref "R21") (pin "1") (pinfunction "1_1") (pintype "passive"))
      (node (ref "R23") (pin "1") (pinfunction "1_1") (pintype "passive"))
    )
    (net (code "34") (name "Net-(IC3B-IN)") (class "Default")
      (node (ref "IC3") (pin "7") (pinfunction "IN_7") (pintype "input"))
      (node (ref "R26") (pin "2") (pinfunction "2_2") (pintype "passive"))
      (node (ref "R28") (pin "1") (pinfunction "1_1") (pintype "passive"))
    )
    (net (code "35") (name "Net-(IC3C-CTRL)") (class "Default")
      (node (ref "C20") (pin "2") (pinfunction "2_2") (pintype "passive"))
      (node (ref "IC3") (pin "11") (pinfunction "CTRL_11") (pintype "input"))
      (node (ref "IC3") (pin "14") (pinfunction "CTRL_14") (pintype "input"))
      (node (ref "IC5") (pin "1") (pinfunction "OUT_1") (pintype "output"))
    )
    (net (code "36") (name "Net-(IC3C-IN)") (class "Default")
      (node (ref "IC3") (pin "10") (pinfunction "IN_10") (pintype "input"))
      (node (ref "R43") (pin "2") (pinfunction "2_2") (pintype "passive"))
      (node (ref "R44") (pin "1") (pinfunction "1_1") (pintype "passive"))
    )
    (net (code "37") (name "Net-(IC3D-IN)") (class "Default")
      (node (ref "IC3") (pin "15") (pinfunction "IN_15") (pintype "input"))
      (node (ref "R34") (pin "1") (pinfunction "1_1") (pintype "passive"))
      (node (ref "R36") (pin "2") (pinfunction "2_2") (pintype "passive"))
    )
    (net (code "38") (name "Net-(IC3D-OUT)") (class "Default")
      (node (ref "C20") (pin "1") (pinfunction "1_1") (pintype "passive"))
      (node (ref "IC3") (pin "13") (pinfunction "OUT_13") (pintype "output"))
      (node (ref "IC5") (pin "2") (pinfunction "-IN_2") (pintype "input"))
      (node (ref "R22") (pin "1") (pinfunction "1_1") (pintype "passive"))
      (node (ref "R24") (pin "1") (pinfunction "1_1") (pintype "passive"))
    )
    (net (code "39") (name "Net-(IC3E-MODE)") (class "Default")
      (node (ref "IC3") (pin "1") (pinfunction "MODE_1") (pintype "input"))
      (node (ref "R35") (pin "2") (pinfunction "2_2") (pintype "passive"))
    )
    (net (code "40") (name "Net-(IC4B--IN)") (class "Default")
      (node (ref "IC4") (pin "6") (pinfunction "-IN_6") (pintype "input"))
      (node (ref "R4") (pin "P$1") (pinfunction "E_P$1") (pintype "passive"))
      (node (ref "R41") (pin "2") (pinfunction "2_2") (pintype "passive"))
    )
    (net (code "41") (name "Net-(IC4B-OUT)") (class "Default")
      (node (ref "IC4") (pin "7") (pinfunction "OUT_7") (pintype "output"))
      (node (ref "R39") (pin "2") (pinfunction "2_2") (pintype "passive"))
      (node (ref "R41") (pin "1") (pinfunction "1_1") (pintype "passive"))
    )
    (net (code "42") (name "Net-(IC4C--IN)") (class "Default")
      (node (ref "C23") (pin "2") (pinfunction "2_2") (pintype "passive"))
      (node (ref "IC4") (pin "9") (pinfunction "-IN_9") (pintype "input"))
      (node (ref "R2") (pin "P$1") (pinfunction "E_P$1") (pintype "passive"))
      (node (ref "R39") (pin "1") (pinfunction "1_1") (pintype "passive"))
      (node (ref "R4") (pin "P$3") (pinfunction "A_P$3") (pintype "passive"))
      (node (ref "R48") (pin "2") (pinfunction "2_2") (pintype "passive"))
      (node (ref "R53") (pin "1") (pinfunction "1_1") (pintype "passive"))
    )
    (net (code "43") (name "Net-(IC4C-OUT)") (class "Default")
      (node (ref "C23") (pin "1") (pinfunction "1_1") (pintype "passive"))
      (node (ref "IC4") (pin "8") (pinfunction "OUT_8") (pintype "output"))
      (node (ref "R28") (pin "2") (pinfunction "2_2") (pintype "passive"))
      (node (ref "R48") (pin "1") (pinfunction "1_1") (pintype "passive"))
      (node (ref "R49") (pin "2") (pinfunction "2_2") (pintype "passive"))
      (node (ref "R50") (pin "2") (pinfunction "2_2") (pintype "passive"))
    )
    (net (code "44") (name "Net-(IC4D-+IN)") (class "Default")
      (node (ref "IC4") (pin "12") (pinfunction "+IN_12") (pintype "input"))
      (node (ref "R49") (pin "1") (pinfunction "1_1") (pintype "passive"))
      (node (ref "R51") (pin "1") (pinfunction "1_1") (pintype "passive"))
    )
    (net (code "45") (name "Net-(IC4D--IN)") (class "Default")
      (node (ref "IC4") (pin "13") (pinfunction "-IN_13") (pintype "input"))
      (node (ref "LED2") (pin "A") (pinfunction "A_A") (pintype "passive"))
      (node (ref "R58") (pin "1") (pinfunction "1_1") (pintype "passive"))
    )
    (net (code "46") (name "Net-(IC4D-OUT)") (class "Default")
      (node (ref "IC4") (pin "14") (pinfunction "OUT_14") (pintype "output"))
      (node (ref "LED2") (pin "K") (pinfunction "C_K") (pintype "passive"))
    )
    (net (code "47") (name "Net-(IC5B--IN)") (class "Default")
      (node (ref "IC5") (pin "6") (pinfunction "-IN_6") (pintype "input"))
      (node (ref "R3") (pin "P$1") (pinfunction "E_P$1") (pintype "passive"))
      (node (ref "R42") (pin "2") (pinfunction "2_2") (pintype "passive"))
    )
    (net (code "48") (name "Net-(IC5B-OUT)") (class "Default")
      (node (ref "IC5") (pin "7") (pinfunction "OUT_7") (pintype "output"))
      (node (ref "R40") (pin "2") (pinfunction "2_2") (pintype "passive"))
      (node (ref "R42") (pin "1") (pinfunction "1_1") (pintype "passive"))
    )
    (net (code "49") (name "Net-(IC5C--IN)") (class "Default")
      (node (ref "C22") (pin "2") (pinfunction "2_2") (pintype "passive"))
      (node (ref "IC5") (pin "9") (pinfunction "-IN_9") (pintype "input"))
      (node (ref "R1") (pin "P$1") (pinfunction "E_P$1") (pintype "passive"))
      (node (ref "R3") (pin "P$3") (pinfunction "A_P$3") (pintype "passive"))
      (node (ref "R40") (pin "1") (pinfunction "1_1") (pintype "passive"))
      (node (ref "R47") (pin "2") (pinfunction "2_2") (pintype "passive"))
      (node (ref "R54") (pin "1") (pinfunction "1_1") (pintype "passive"))
    )
    (net (code "50") (name "Net-(IC5C-OUT)") (class "Default")
      (node (ref "C22") (pin "1") (pinfunction "1_1") (pintype "passive"))
      (node (ref "IC5") (pin "8") (pinfunction "OUT_8") (pintype "output"))
      (node (ref "R44") (pin "2") (pinfunction "2_2") (pintype "passive"))
      (node (ref "R45") (pin "2") (pinfunction "2_2") (pintype "passive"))
      (node (ref "R47") (pin "1") (pinfunction "1_1") (pintype "passive"))
      (node (ref "R8") (pin "2") (pinfunction "2_2") (pintype "passive"))
    )
    (net (code "51") (name "Net-(IC5D-+IN)") (class "Default")
      (node (ref "IC5") (pin "12") (pinfunction "+IN_12") (pintype "input"))
      (node (ref "R45") (pin "1") (pinfunction "1_1") (pintype "passive"))
      (node (ref "R46") (pin "1") (pinfunction "1_1") (pintype "passive"))
    )
    (net (code "52") (name "Net-(IC5D--IN)") (class "Default")
      (node (ref "IC5") (pin "13") (pinfunction "-IN_13") (pintype "input"))
      (node (ref "LED1") (pin "A") (pinfunction "A_A") (pintype "passive"))
      (node (ref "R59") (pin "1") (pinfunction "1_1") (pintype "passive"))
    )
    (net (code "53") (name "Net-(IC5D-OUT)") (class "Default")
      (node (ref "IC5") (pin "14") (pinfunction "OUT_14") (pintype "output"))
      (node (ref "LED1") (pin "K") (pinfunction "C_K") (pintype "passive"))
    )
    (net (code "54") (name "Net-(IN_1-2)") (class "Default")
      (node (ref "IN_1") (pin "P2") (pinfunction "2_P2") (pintype "passive"))
      (node (ref "R27") (pin "2") (pinfunction "2_2") (pintype "passive"))
    )
    (net (code "55") (name "Net-(IN_1-3)") (class "Default")
      (node (ref "IN_1") (pin "P3") (pinfunction "3_P3") (pintype "passive"))
      (node (ref "R22") (pin "2") (pinfunction "2_2") (pintype "passive"))
    )
    (net (code "56") (name "Net-(IN_2-2)") (class "Default")
      (node (ref "IN_2") (pin "P2") (pinfunction "2_P2") (pintype "passive"))
      (node (ref "R25") (pin "2") (pinfunction "2_2") (pintype "passive"))
    )
    (net (code "57") (name "Net-(IN_2-3)") (class "Default")
      (node (ref "IN_2") (pin "P3") (pinfunction "3_P3") (pintype "passive"))
      (node (ref "R21") (pin "2") (pinfunction "2_2") (pintype "passive"))
    )
    (net (code "58") (name "Net-(L1-Pad2)") (class "Default")
      (node (ref "L1") (pin "2") (pinfunction "2_2") (pintype "passive"))
      (node (ref "P1") (pin "1") (pinfunction "1_1") (pintype "bidirectional"))
    )
    (net (code "59") (name "Net-(OUT_1-2)") (class "Default")
      (node (ref "OUT_1") (pin "P2") (pinfunction "2_P2") (pintype "passive"))
      (node (ref "R14") (pin "2") (pinfunction "2_2") (pintype "passive"))
    )
    (net (code "60") (name "Net-(OUT_1-3)") (class "Default")
      (node (ref "OUT_1") (pin "P3") (pinfunction "3_P3") (pintype "passive"))
      (node (ref "R6") (pin "1") (pinfunction "1_1") (pintype "passive"))
    )
    (net (code "61") (name "Net-(OUT_2-2)") (class "Default")
      (node (ref "OUT_2") (pin "P2") (pinfunction "2_P2") (pintype "passive"))
      (node (ref "R15") (pin "2") (pinfunction "2_2") (pintype "passive"))
    )
    (net (code "62") (name "Net-(OUT_2-3)") (class "Default")
      (node (ref "OUT_2") (pin "P3") (pinfunction "3_P3") (pintype "passive"))
      (node (ref "R5") (pin "1") (pinfunction "1_1") (pintype "passive"))
    )
    (net (code "63") (name "Net-(P1-Pad2)") (class "Default")
      (node (ref "P1") (pin "2") (pinfunction "2_2") (pintype "bidirectional"))
      (node (ref "POWER!") (pin "1") (pinfunction "-12V_1") (pintype "bidirectional"))
      (node (ref "POWER!") (pin "2") (pinfunction "-12V_2") (pintype "bidirectional"))
    )
    (net (code "64") (name "Net-(R1-S)") (class "Default")
      (node (ref "R1") (pin "P$2") (pinfunction "S_P$2") (pintype "passive"))
      (node (ref "R61") (pin "1") (pinfunction "1_1") (pintype "passive"))
    )
    (net (code "65") (name "Net-(R2-S)") (class "Default")
      (node (ref "R2") (pin "P$2") (pinfunction "S_P$2") (pintype "passive"))
      (node (ref "R60") (pin "1") (pinfunction "1_1") (pintype "passive"))
    )
    (net (code "66") (name "Net-(R3-S)") (class "Default")
      (node (ref "R3") (pin "P$2") (pinfunction "S_P$2") (pintype "passive"))
      (node (ref "R55") (pin "1") (pinfunction "1_1") (pintype "passive"))
    )
    (net (code "67") (name "Net-(R4-S)") (class "Default")
      (node (ref "R4") (pin "P$2") (pinfunction "S_P$2") (pintype "passive"))
      (node (ref "R52") (pin "1") (pinfunction "1_1") (pintype "passive"))
    )
    (net (code "68") (name "VCC") (class "Default")
      (node (ref "C1") (pin "+") (pinfunction "+_+") (pintype "passive"))
      (node (ref "C10") (pin "1") (pinfunction "1_1") (pintype "passive"))
      (node (ref "C12") (pin "1") (pinfunction "1_1") (pintype "passive"))
      (node (ref "C24") (pin "1") (pinfunction "1_1") (pintype "passive"))
      (node (ref "C5") (pin "1") (pinfunction "1_1") (pintype "passive"))
      (node (ref "C6") (pin "1") (pinfunction "1_1") (pintype "passive"))
      (node (ref "C7") (pin "1") (pinfunction "1_1") (pintype "passive"))
      (node (ref "IC1") (pin "4") (pinfunction "V+_4") (pintype "power_in"))
      (node (ref "IC2") (pin "4") (pinfunction "V+_4") (pintype "power_in"))
      (node (ref "IC3") (pin "16") (pinfunction "V+_16") (pintype "power_in"))
      (node (ref "IC4") (pin "4") (pinfunction "V+_4") (pintype "power_in"))
      (node (ref "IC5") (pin "4") (pinfunction "V+_4") (pintype "power_in"))
      (node (ref "L2") (pin "1") (pinfunction "1_1") (pintype "passive"))
      (node (ref "R35") (pin "1") (pinfunction "1_1") (pintype "passive"))
      (node (ref "R56") (pin "1") (pinfunction "1_1") (pintype "passive"))
    )
    (net (code "69") (name "VEE") (class "Default")
      (node (ref "C11") (pin "2") (pinfunction "2_2") (pintype "passive"))
      (node (ref "C2") (pin "-") (pinfunction "-_-") (pintype "passive"))
      (node (ref "C25") (pin "1") (pinfunction "1_1") (pintype "passive"))
      (node (ref "C3") (pin "2") (pinfunction "2_2") (pintype "passive"))
      (node (ref "C4") (pin "2") (pinfunction "2_2") (pintype "passive"))
      (node (ref "C8") (pin "2") (pinfunction "2_2") (pintype "passive"))
      (node (ref "C9") (pin "2") (pinfunction "2_2") (pintype "passive"))
      (node (ref "D2") (pin "A") (pinfunction "A_A") (pintype "passive"))
      (node (ref "IC1") (pin "11") (pinfunction "V-_11") (pintype "power_in"))
      (node (ref "IC2") (pin "11") (pinfunction "V-_11") (pintype "power_in"))
      (node (ref "IC3") (pin "9") (pinfunction "V-_9") (pintype "power_in"))
      (node (ref "IC4") (pin "11") (pinfunction "V-_11") (pintype "power_in"))
      (node (ref "IC5") (pin "11") (pinfunction "V-_11") (pintype "power_in"))
      (node (ref "L1") (pin "1") (pinfunction "1_1") (pintype "passive"))
      (node (ref "R57") (pin "1") (pinfunction "1_1") (pintype "passive"))
    )
  )
)
